# FMC_CONN_A1.net
KiCad netlist of a schematic drawn in Altium Designer
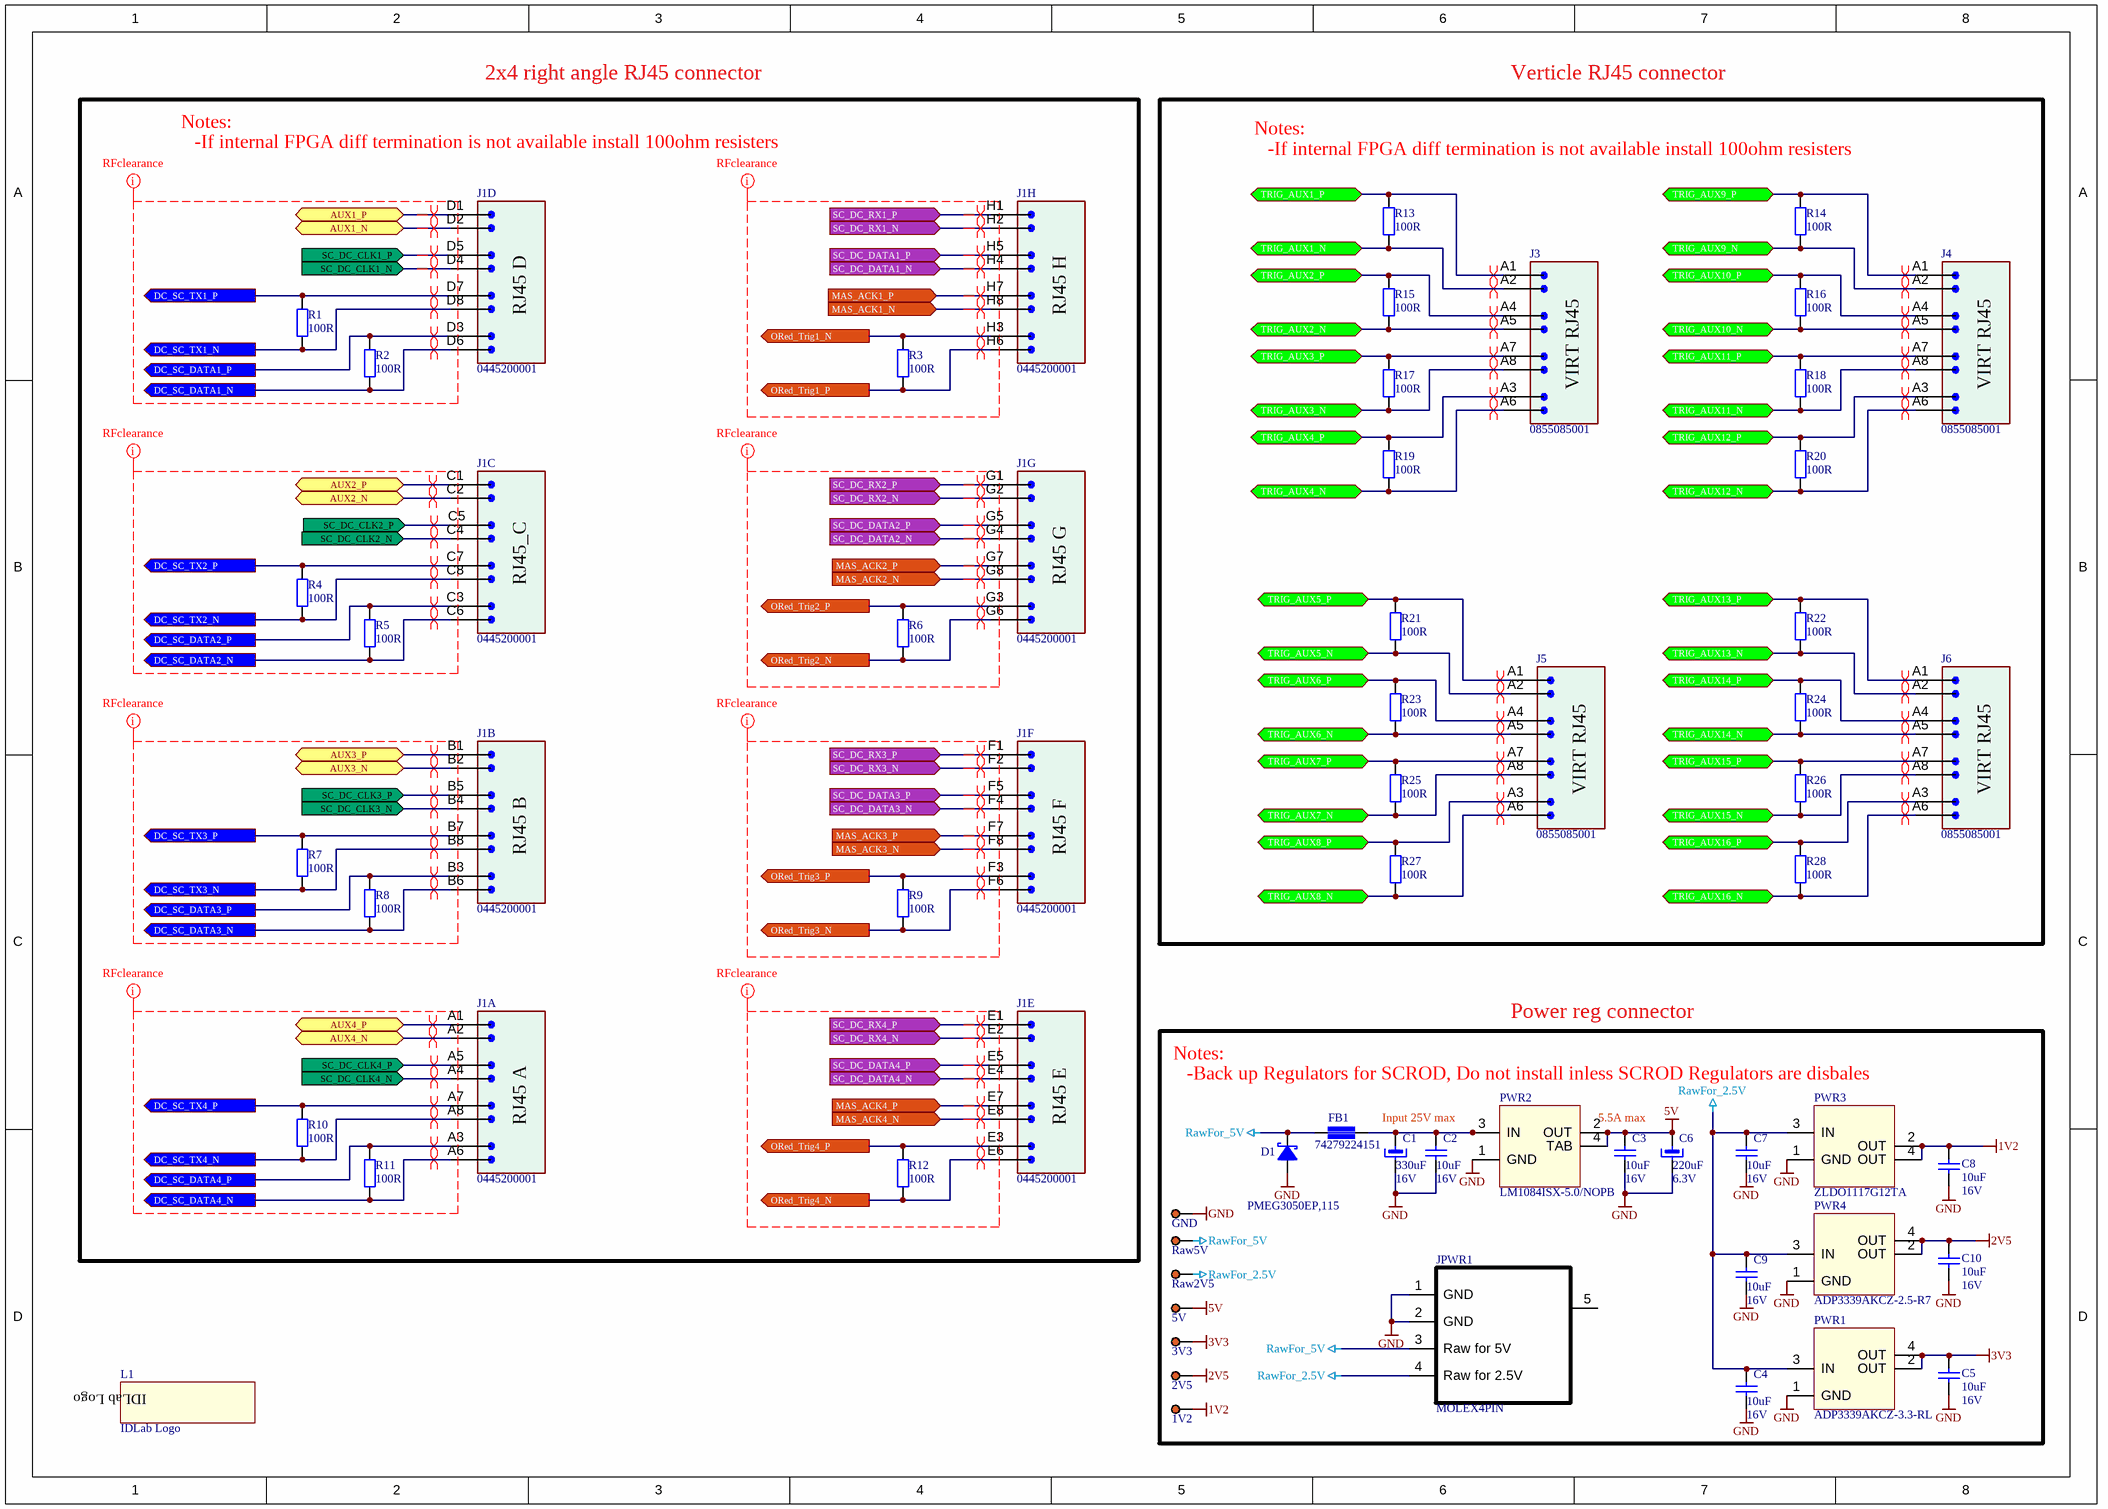
[diagram p0: FMC_CONN_A1.SchDoc]

(export (version "E")
  (design (tool "Eeschema 10.0.6"))
  (components
    (comp (ref "1V2")
      (value "SP1.5S")
      (footprint "SP1.5SQ")
      (description "Wire solder pin 1.5mm")
      (libsource (lib "Connectors_Old") (part "SP1.5S"))
    )
    (comp (ref "2V5")
      (value "SP1.5S")
      (footprint "SP1.5SQ")
      (description "Wire solder pin 1.5mm")
      (libsource (lib "Connectors_Old") (part "SP1.5S"))
    )
    (comp (ref "3V3")
      (value "SP1.5S")
      (footprint "SP1.5SQ")
      (description "Wire solder pin 1.5mm")
      (libsource (lib "Connectors_Old") (part "SP1.5S"))
    )
    (comp (ref "5V")
      (value "SP1.5S")
      (footprint "SP1.5SQ")
      (description "Wire solder pin 1.5mm")
      (libsource (lib "Connectors_Old") (part "SP1.5S"))
    )
    (comp (ref "C1")
      (value "330uF")
      (footprint "CTC-D7343-43")
      (description "330µF Molded Tantalum - Polymer Capacitors 16V")
      (fields (field (name "MANUFACTURER") "Kemet") (field (name "VOLTAGE RATING") "16V"))
      (libsource (lib "BMD") (part "CAPT7343_330U_16V"))
    )
    (comp (ref "C2")
      (value "10uF")
      (footprint "CC1206N1R")
      (description "10µF 16V Ceramic Capacitor X7R 1206")
      (fields (field (name "MANUFACTURER") "TDK") (field (name "VOLTAGE RATING") "16V"))
      (libsource (lib "BMD") (part "CAPCC1206_10U_16VX7R"))
    )
    (comp (ref "C3")
      (value "10uF")
      (footprint "CC1206N1R")
      (description "10µF 16V Ceramic Capacitor X7R 1206")
      (fields (field (name "MANUFACTURER") "TDK") (field (name "VOLTAGE RATING") "16V"))
      (libsource (lib "BMD") (part "CAPCC1206_10U_16VX7R"))
    )
    (comp (ref "C4")
      (value "10uF")
      (footprint "CC1206N1R")
      (description "10µF 16V Ceramic Capacitor X7R 1206")
      (fields (field (name "MANUFACTURER") "TDK") (field (name "VOLTAGE RATING") "16V"))
      (libsource (lib "BMD") (part "CAPCC1206_10U_16VX7R"))
    )
    (comp (ref "C5")
      (value "10uF")
      (footprint "CC1206N1R")
      (description "10µF 16V Ceramic Capacitor X7R 1206")
      (fields (field (name "MANUFACTURER") "TDK") (field (name "VOLTAGE RATING") "16V"))
      (libsource (lib "BMD") (part "CAPCC1206_10U_16VX7R"))
    )
    (comp (ref "C6")
      (value "220uF")
      (footprint "CTC-D7343-43")
      (description "220µF 6.3V Aluminum - Polymer Capacitors")
      (fields (field (name "MANUFACTURER") "Panasonic") (field (name "VOLTAGE RATING") "6.3V"))
      (libsource (lib "BMD") (part "CAPT7343_220U_6.3V"))
    )
    (comp (ref "C7")
      (value "10uF")
      (footprint "CC1206N1R")
      (description "10µF 16V Ceramic Capacitor X7R 1206")
      (fields (field (name "MANUFACTURER") "TDK") (field (name "VOLTAGE RATING") "16V"))
      (libsource (lib "BMD") (part "CAPCC1206_10U_16VX7R"))
    )
    (comp (ref "C8")
      (value "10uF")
      (footprint "CC1206N1R")
      (description "10µF 16V Ceramic Capacitor X7R 1206")
      (fields (field (name "MANUFACTURER") "TDK") (field (name "VOLTAGE RATING") "16V"))
      (libsource (lib "BMD") (part "CAPCC1206_10U_16VX7R"))
    )
    (comp (ref "C9")
      (value "10uF")
      (footprint "CC1206N1R")
      (description "10µF 16V Ceramic Capacitor X7R 1206")
      (fields (field (name "MANUFACTURER") "TDK") (field (name "VOLTAGE RATING") "16V"))
      (libsource (lib "BMD") (part "CAPCC1206_10U_16VX7R"))
    )
    (comp (ref "C10")
      (value "10uF")
      (footprint "CC1206N1R")
      (description "10µF 16V Ceramic Capacitor X7R 1206")
      (fields (field (name "MANUFACTURER") "TDK") (field (name "VOLTAGE RATING") "16V"))
      (libsource (lib "BMD") (part "CAPCC1206_10U_16VX7R"))
    )
    (comp (ref "D1")
      (value "PMEG3050EP,115")
      (footprint "SOD128")
      (description "DIODE SCHOTTKY 30V 5A SOD128  500ns 0.36Vf")
      (fields (field (name "MANUFACTURER") "NXP"))
      (libsource (lib "BMD") (part "Schottky_Diodes_5A_30V"))
    )
    (comp (ref "FB1")
      (value "74279224151")
      (footprint "FB2220N1R")
      (description "Feritte filter smd 2220 5A 10mRdc 150Rac")
      (fields (field (name "MANUFACTURER") "Wurth"))
      (libsource (lib "Induct-filter") (part "FB2220-74279224151"))
    )
    (comp (ref "GND")
      (value "SP1.5S")
      (footprint "SP1.5SQ")
      (description "Wire solder pin 1.5mm")
      (libsource (lib "Connectors_Old") (part "SP1.5S"))
    )
    (comp (ref "J1")
      (value "0445200001")
      (footprint "2X4 RJ45")
      (description "CONN MOD JACK 8P8C R/A SHIELDED")
      (fields (field (name "MANUFACTURER") "Molex, LLC"))
      (libsource (lib "IDlab") (part "2x4 RJ45 CONN"))
    )
    (comp (ref "J3")
      (value "0855085001")
      (footprint "VIRT RJ45")
      (description "CONN MOD JACK 8P8C R/A SHIELDED")
      (fields (field (name "MANUFACTURER") "Molex, LLC"))
      (libsource (lib "IDlab") (part "VIRT RJ45 CONN"))
    )
    (comp (ref "J4")
      (value "0855085001")
      (footprint "VIRT RJ45")
      (description "CONN MOD JACK 8P8C R/A SHIELDED")
      (fields (field (name "MANUFACTURER") "Molex, LLC"))
      (libsource (lib "IDlab") (part "VIRT RJ45 CONN"))
    )
    (comp (ref "J5")
      (value "0855085001")
      (footprint "VIRT RJ45")
      (description "CONN MOD JACK 8P8C R/A SHIELDED")
      (fields (field (name "MANUFACTURER") "Molex, LLC"))
      (libsource (lib "IDlab") (part "VIRT RJ45 CONN"))
    )
    (comp (ref "J6")
      (value "0855085001")
      (footprint "VIRT RJ45")
      (description "CONN MOD JACK 8P8C R/A SHIELDED")
      (fields (field (name "MANUFACTURER") "Molex, LLC"))
      (libsource (lib "IDlab") (part "VIRT RJ45 CONN"))
    )
    (comp (ref "JPWR1")
      (value "MOLEX4PIN")
      (footprint "PcbLib1:MOLEX_4PIN")
      (libsource (lib "Transition_Board") (part "MOLEX4PIN"))
    )
    (comp (ref "L1")
      (value "IDLab Logo")
      (footprint "IDLab logo")
      (libsource (lib "BMD") (part "IDLab Logo"))
    )
    (comp (ref "PWR1")
      (value "ADP3339AKCZ-3.3-RL")
      (footprint "SOT223")
      (description "IC REG LDO 3.3V 1.5A SOT223-3")
      (fields (field (name "MANUFACTURER") "Analog Devices Inc."))
      (libsource (lib "BMD") (part "3V3 REG LDO"))
    )
    (comp (ref "PWR2")
      (value "LM1084ISX-5.0/NOPB")
      (footprint "TO-263-4 DDPAK")
      (description "IC REG LDO 5V 5A DDPAK/TO-263-3")
      (fields (field (name "MANUFACTURER") "Texas Instruments"))
      (libsource (lib "BMD") (part "5V 5.5A REG LDO"))
    )
    (comp (ref "PWR3")
      (value "ZLDO1117G12TA")
      (footprint "SOT223")
      (description "IC REG LDO 1.2V 1A SOT223-3")
      (fields (field (name "MANUFACTURER") "Diodes Incorporated"))
      (libsource (lib "BMD") (part "1V2 REG LDO"))
    )
    (comp (ref "PWR4")
      (value "ADP3339AKCZ-2.5-R7")
      (footprint "SOT223")
      (description "IC REG LDO 2.5V 1.5A SOT223-3")
      (fields (field (name "MANUFACTURER") "Analog Devices Inc."))
      (libsource (lib "BMD") (part "2V5 REG LDO"))
    )
    (comp (ref "R1")
      (value "100R")
      (footprint "RC0402N1R")
      (description "RES SMD 100 OHM 1% 1/10W 0402")
      (fields (field (name "MANUFACTURER") "Panasonic"))
      (libsource (lib "BMD") (part "RES0402-100R-1%100PPM"))
    )
    (comp (ref "R2")
      (value "100R")
      (footprint "RC0402N1R")
      (description "RES SMD 100 OHM 1% 1/10W 0402")
      (fields (field (name "MANUFACTURER") "Panasonic"))
      (libsource (lib "BMD") (part "RES0402-100R-1%100PPM"))
    )
    (comp (ref "R3")
      (value "100R")
      (footprint "RC0402N1R")
      (description "RES SMD 100 OHM 1% 1/10W 0402")
      (fields (field (name "MANUFACTURER") "Panasonic"))
      (libsource (lib "BMD") (part "RES0402-100R-1%100PPM"))
    )
    (comp (ref "R4")
      (value "100R")
      (footprint "RC0402N1R")
      (description "RES SMD 100 OHM 1% 1/10W 0402")
      (fields (field (name "MANUFACTURER") "Panasonic"))
      (libsource (lib "BMD") (part "RES0402-100R-1%100PPM"))
    )
    (comp (ref "R5")
      (value "100R")
      (footprint "RC0402N1R")
      (description "RES SMD 100 OHM 1% 1/10W 0402")
      (fields (field (name "MANUFACTURER") "Panasonic"))
      (libsource (lib "BMD") (part "RES0402-100R-1%100PPM"))
    )
    (comp (ref "R6")
      (value "100R")
      (footprint "RC0402N1R")
      (description "RES SMD 100 OHM 1% 1/10W 0402")
      (fields (field (name "MANUFACTURER") "Panasonic"))
      (libsource (lib "BMD") (part "RES0402-100R-1%100PPM"))
    )
    (comp (ref "R7")
      (value "100R")
      (footprint "RC0402N1R")
      (description "RES SMD 100 OHM 1% 1/10W 0402")
      (fields (field (name "MANUFACTURER") "Panasonic"))
      (libsource (lib "BMD") (part "RES0402-100R-1%100PPM"))
    )
    (comp (ref "R8")
      (value "100R")
      (footprint "RC0402N1R")
      (description "RES SMD 100 OHM 1% 1/10W 0402")
      (fields (field (name "MANUFACTURER") "Panasonic"))
      (libsource (lib "BMD") (part "RES0402-100R-1%100PPM"))
    )
    (comp (ref "R9")
      (value "100R")
      (footprint "RC0402N1R")
      (description "RES SMD 100 OHM 1% 1/10W 0402")
      (fields (field (name "MANUFACTURER") "Panasonic"))
      (libsource (lib "BMD") (part "RES0402-100R-1%100PPM"))
    )
    (comp (ref "R10")
      (value "100R")
      (footprint "RC0402N1R")
      (description "RES SMD 100 OHM 1% 1/10W 0402")
      (fields (field (name "MANUFACTURER") "Panasonic"))
      (libsource (lib "BMD") (part "RES0402-100R-1%100PPM"))
    )
    (comp (ref "R11")
      (value "100R")
      (footprint "RC0402N1R")
      (description "RES SMD 100 OHM 1% 1/10W 0402")
      (fields (field (name "MANUFACTURER") "Panasonic"))
      (libsource (lib "BMD") (part "RES0402-100R-1%100PPM"))
    )
    (comp (ref "R12")
      (value "100R")
      (footprint "RC0402N1R")
      (description "RES SMD 100 OHM 1% 1/10W 0402")
      (fields (field (name "MANUFACTURER") "Panasonic"))
      (libsource (lib "BMD") (part "RES0402-100R-1%100PPM"))
    )
    (comp (ref "R13")
      (value "100R")
      (footprint "RC0402N1R")
      (description "RES SMD 100 OHM 1% 1/10W 0402")
      (fields (field (name "MANUFACTURER") "Panasonic"))
      (libsource (lib "BMD") (part "RES0402-100R-1%100PPM"))
    )
    (comp (ref "R14")
      (value "100R")
      (footprint "RC0402N1R")
      (description "RES SMD 100 OHM 1% 1/10W 0402")
      (fields (field (name "MANUFACTURER") "Panasonic"))
      (libsource (lib "BMD") (part "RES0402-100R-1%100PPM"))
    )
    (comp (ref "R15")
      (value "100R")
      (footprint "RC0402N1R")
      (description "RES SMD 100 OHM 1% 1/10W 0402")
      (fields (field (name "MANUFACTURER") "Panasonic"))
      (libsource (lib "BMD") (part "RES0402-100R-1%100PPM"))
    )
    (comp (ref "R16")
      (value "100R")
      (footprint "RC0402N1R")
      (description "RES SMD 100 OHM 1% 1/10W 0402")
      (fields (field (name "MANUFACTURER") "Panasonic"))
      (libsource (lib "BMD") (part "RES0402-100R-1%100PPM"))
    )
    (comp (ref "R17")
      (value "100R")
      (footprint "RC0402N1R")
      (description "RES SMD 100 OHM 1% 1/10W 0402")
      (fields (field (name "MANUFACTURER") "Panasonic"))
      (libsource (lib "BMD") (part "RES0402-100R-1%100PPM"))
    )
    (comp (ref "R18")
      (value "100R")
      (footprint "RC0402N1R")
      (description "RES SMD 100 OHM 1% 1/10W 0402")
      (fields (field (name "MANUFACTURER") "Panasonic"))
      (libsource (lib "BMD") (part "RES0402-100R-1%100PPM"))
    )
    (comp (ref "R19")
      (value "100R")
      (footprint "RC0402N1R")
      (description "RES SMD 100 OHM 1% 1/10W 0402")
      (fields (field (name "MANUFACTURER") "Panasonic"))
      (libsource (lib "BMD") (part "RES0402-100R-1%100PPM"))
    )
    (comp (ref "R20")
      (value "100R")
      (footprint "RC0402N1R")
      (description "RES SMD 100 OHM 1% 1/10W 0402")
      (fields (field (name "MANUFACTURER") "Panasonic"))
      (libsource (lib "BMD") (part "RES0402-100R-1%100PPM"))
    )
    (comp (ref "R21")
      (value "100R")
      (footprint "RC0402N1R")
      (description "RES SMD 100 OHM 1% 1/10W 0402")
      (fields (field (name "MANUFACTURER") "Panasonic"))
      (libsource (lib "BMD") (part "RES0402-100R-1%100PPM"))
    )
    (comp (ref "R22")
      (value "100R")
      (footprint "RC0402N1R")
      (description "RES SMD 100 OHM 1% 1/10W 0402")
      (fields (field (name "MANUFACTURER") "Panasonic"))
      (libsource (lib "BMD") (part "RES0402-100R-1%100PPM"))
    )
    (comp (ref "R23")
      (value "100R")
      (footprint "RC0402N1R")
      (description "RES SMD 100 OHM 1% 1/10W 0402")
      (fields (field (name "MANUFACTURER") "Panasonic"))
      (libsource (lib "BMD") (part "RES0402-100R-1%100PPM"))
    )
    (comp (ref "R24")
      (value "100R")
      (footprint "RC0402N1R")
      (description "RES SMD 100 OHM 1% 1/10W 0402")
      (fields (field (name "MANUFACTURER") "Panasonic"))
      (libsource (lib "BMD") (part "RES0402-100R-1%100PPM"))
    )
    (comp (ref "R25")
      (value "100R")
      (footprint "RC0402N1R")
      (description "RES SMD 100 OHM 1% 1/10W 0402")
      (fields (field (name "MANUFACTURER") "Panasonic"))
      (libsource (lib "BMD") (part "RES0402-100R-1%100PPM"))
    )
    (comp (ref "R26")
      (value "100R")
      (footprint "RC0402N1R")
      (description "RES SMD 100 OHM 1% 1/10W 0402")
      (fields (field (name "MANUFACTURER") "Panasonic"))
      (libsource (lib "BMD") (part "RES0402-100R-1%100PPM"))
    )
    (comp (ref "R27")
      (value "100R")
      (footprint "RC0402N1R")
      (description "RES SMD 100 OHM 1% 1/10W 0402")
      (fields (field (name "MANUFACTURER") "Panasonic"))
      (libsource (lib "BMD") (part "RES0402-100R-1%100PPM"))
    )
    (comp (ref "R28")
      (value "100R")
      (footprint "RC0402N1R")
      (description "RES SMD 100 OHM 1% 1/10W 0402")
      (fields (field (name "MANUFACTURER") "Panasonic"))
      (libsource (lib "BMD") (part "RES0402-100R-1%100PPM"))
    )
    (comp (ref "Raw2V5")
      (value "SP1.5S")
      (footprint "SP1.5SQ")
      (description "Wire solder pin 1.5mm")
      (libsource (lib "Connectors_Old") (part "SP1.5S"))
    )
    (comp (ref "Raw5V")
      (value "SP1.5S")
      (footprint "SP1.5SQ")
      (description "Wire solder pin 1.5mm")
      (libsource (lib "Connectors_Old") (part "SP1.5S"))
    )
  )
  (nets
    (net (code "1") (name "/AUX1_N") (class "Default")
      (node (ref "J1") (pin "D2") (pinfunction "D2_D2") (pintype "passive"))
    )
    (net (code "2") (name "/AUX1_P") (class "Default")
      (node (ref "J1") (pin "D1") (pinfunction "D1_D1") (pintype "passive"))
    )
    (net (code "3") (name "/AUX2_N") (class "Default")
      (node (ref "J1") (pin "C2") (pinfunction "C2_C2") (pintype "passive"))
    )
    (net (code "4") (name "/AUX2_P") (class "Default")
      (node (ref "J1") (pin "C1") (pinfunction "C1_C1") (pintype "passive"))
    )
    (net (code "5") (name "/AUX3_N") (class "Default")
      (node (ref "J1") (pin "B2") (pinfunction "B2_B2") (pintype "passive"))
    )
    (net (code "6") (name "/AUX3_P") (class "Default")
      (node (ref "J1") (pin "B1") (pinfunction "B1_B1") (pintype "passive"))
    )
    (net (code "7") (name "/AUX4_N") (class "Default")
      (node (ref "J1") (pin "A2") (pinfunction "A2_A2") (pintype "passive"))
    )
    (net (code "8") (name "/AUX4_P") (class "Default")
      (node (ref "J1") (pin "A1") (pinfunction "A1_A1") (pintype "passive"))
    )
    (net (code "9") (name "/DC_SC_DATA1_N") (class "Default")
      (node (ref "J1") (pin "D6") (pinfunction "D6_D6") (pintype "passive"))
      (node (ref "R2") (pin "1") (pinfunction "1_1") (pintype "passive"))
    )
    (net (code "10") (name "/DC_SC_DATA1_P") (class "Default")
      (node (ref "J1") (pin "D3") (pinfunction "D3_D3") (pintype "passive"))
      (node (ref "R2") (pin "2") (pinfunction "2_2") (pintype "passive"))
    )
    (net (code "11") (name "/DC_SC_DATA2_N") (class "Default")
      (node (ref "J1") (pin "C6") (pinfunction "C6_C6") (pintype "passive"))
      (node (ref "R5") (pin "1") (pinfunction "1_1") (pintype "passive"))
    )
    (net (code "12") (name "/DC_SC_DATA2_P") (class "Default")
      (node (ref "J1") (pin "C3") (pinfunction "C3_C3") (pintype "passive"))
      (node (ref "R5") (pin "2") (pinfunction "2_2") (pintype "passive"))
    )
    (net (code "13") (name "/DC_SC_DATA3_N") (class "Default")
      (node (ref "J1") (pin "B6") (pinfunction "B6_B6") (pintype "passive"))
      (node (ref "R8") (pin "1") (pinfunction "1_1") (pintype "passive"))
    )
    (net (code "14") (name "/DC_SC_DATA3_P") (class "Default")
      (node (ref "J1") (pin "B3") (pinfunction "B3_B3") (pintype "passive"))
      (node (ref "R8") (pin "2") (pinfunction "2_2") (pintype "passive"))
    )
    (net (code "15") (name "/DC_SC_DATA4_N") (class "Default")
      (node (ref "J1") (pin "A6") (pinfunction "A6_A6") (pintype "passive"))
      (node (ref "R11") (pin "1") (pinfunction "1_1") (pintype "passive"))
    )
    (net (code "16") (name "/DC_SC_DATA4_P") (class "Default")
      (node (ref "J1") (pin "A3") (pinfunction "A3_A3") (pintype "passive"))
      (node (ref "R11") (pin "2") (pinfunction "2_2") (pintype "passive"))
    )
    (net (code "17") (name "/DC_SC_TX1_N") (class "Default")
      (node (ref "J1") (pin "D8") (pinfunction "D8_D8") (pintype "passive"))
      (node (ref "R1") (pin "1") (pinfunction "1_1") (pintype "passive"))
    )
    (net (code "18") (name "/DC_SC_TX1_P") (class "Default")
      (node (ref "J1") (pin "D7") (pinfunction "D7_D7") (pintype "passive"))
      (node (ref "R1") (pin "2") (pinfunction "2_2") (pintype "passive"))
    )
    (net (code "19") (name "/DC_SC_TX2_N") (class "Default")
      (node (ref "J1") (pin "C8") (pinfunction "C8_C8") (pintype "passive"))
      (node (ref "R4") (pin "1") (pinfunction "1_1") (pintype "passive"))
    )
    (net (code "20") (name "/DC_SC_TX2_P") (class "Default")
      (node (ref "J1") (pin "C7") (pinfunction "C7_C7") (pintype "passive"))
      (node (ref "R4") (pin "2") (pinfunction "2_2") (pintype "passive"))
    )
    (net (code "21") (name "/DC_SC_TX3_N") (class "Default")
      (node (ref "J1") (pin "B8") (pinfunction "B8_B8") (pintype "passive"))
      (node (ref "R7") (pin "1") (pinfunction "1_1") (pintype "passive"))
    )
    (net (code "22") (name "/DC_SC_TX3_P") (class "Default")
      (node (ref "J1") (pin "B7") (pinfunction "B7_B7") (pintype "passive"))
      (node (ref "R7") (pin "2") (pinfunction "2_2") (pintype "passive"))
    )
    (net (code "23") (name "/DC_SC_TX4_N") (class "Default")
      (node (ref "J1") (pin "A8") (pinfunction "A8_A8") (pintype "passive"))
      (node (ref "R10") (pin "1") (pinfunction "1_1") (pintype "passive"))
    )
    (net (code "24") (name "/DC_SC_TX4_P") (class "Default")
      (node (ref "J1") (pin "A7") (pinfunction "A7_A7") (pintype "passive"))
      (node (ref "R10") (pin "2") (pinfunction "2_2") (pintype "passive"))
    )
    (net (code "25") (name "/MAS_ACK1_N") (class "Default")
      (node (ref "J1") (pin "H8") (pinfunction "H8_H8") (pintype "passive"))
    )
    (net (code "26") (name "/MAS_ACK1_P") (class "Default")
      (node (ref "J1") (pin "H7") (pinfunction "H7_H7") (pintype "passive"))
    )
    (net (code "27") (name "/MAS_ACK2_N") (class "Default")
      (node (ref "J1") (pin "G8") (pinfunction "G8_G8") (pintype "passive"))
    )
    (net (code "28") (name "/MAS_ACK2_P") (class "Default")
      (node (ref "J1") (pin "G7") (pinfunction "G7_G7") (pintype "passive"))
    )
    (net (code "29") (name "/MAS_ACK3_N") (class "Default")
      (node (ref "J1") (pin "F8") (pinfunction "F8_F8") (pintype "passive"))
    )
    (net (code "30") (name "/MAS_ACK3_P") (class "Default")
      (node (ref "J1") (pin "F7") (pinfunction "F7_F7") (pintype "passive"))
    )
    (net (code "31") (name "/MAS_ACK4_N") (class "Default")
      (node (ref "J1") (pin "E8") (pinfunction "E8_E8") (pintype "passive"))
    )
    (net (code "32") (name "/MAS_ACK4_P") (class "Default")
      (node (ref "J1") (pin "E7") (pinfunction "E7_E7") (pintype "passive"))
    )
    (net (code "33") (name "/ORed_Trig1_N") (class "Default")
      (node (ref "J1") (pin "H3") (pinfunction "H3_H3") (pintype "passive"))
      (node (ref "R3") (pin "2") (pinfunction "2_2") (pintype "passive"))
    )
    (net (code "34") (name "/ORed_Trig1_P") (class "Default")
      (node (ref "J1") (pin "H6") (pinfunction "H6_H6") (pintype "passive"))
      (node (ref "R3") (pin "1") (pinfunction "1_1") (pintype "passive"))
    )
    (net (code "35") (name "/ORed_Trig2_N") (class "Default")
      (node (ref "J1") (pin "G6") (pinfunction "G6_G6") (pintype "passive"))
      (node (ref "R6") (pin "1") (pinfunction "1_1") (pintype "passive"))
    )
    (net (code "36") (name "/ORed_Trig2_P") (class "Default")
      (node (ref "J1") (pin "G3") (pinfunction "G3_G3") (pintype "passive"))
      (node (ref "R6") (pin "2") (pinfunction "2_2") (pintype "passive"))
    )
    (net (code "37") (name "/ORed_Trig3_N") (class "Default")
      (node (ref "J1") (pin "F6") (pinfunction "F6_F6") (pintype "passive"))
      (node (ref "R9") (pin "1") (pinfunction "1_1") (pintype "passive"))
    )
    (net (code "38") (name "/ORed_Trig3_P") (class "Default")
      (node (ref "J1") (pin "F3") (pinfunction "F3_F3") (pintype "passive"))
      (node (ref "R9") (pin "2") (pinfunction "2_2") (pintype "passive"))
    )
    (net (code "39") (name "/ORed_Trig4_N") (class "Default")
      (node (ref "J1") (pin "E6") (pinfunction "E6_E6") (pintype "passive"))
      (node (ref "R12") (pin "1") (pinfunction "1_1") (pintype "passive"))
    )
    (net (code "40") (name "/ORed_Trig4_P") (class "Default")
      (node (ref "J1") (pin "E3") (pinfunction "E3_E3") (pintype "passive"))
      (node (ref "R12") (pin "2") (pinfunction "2_2") (pintype "passive"))
    )
    (net (code "41") (name "/SC_DC_CLK1_N") (class "Default")
      (node (ref "J1") (pin "D4") (pinfunction "D4_D4") (pintype "passive"))
    )
    (net (code "42") (name "/SC_DC_CLK1_P") (class "Default")
      (node (ref "J1") (pin "D5") (pinfunction "D5_D5") (pintype "passive"))
    )
    (net (code "43") (name "/SC_DC_CLK2_N") (class "Default")
      (node (ref "J1") (pin "C4") (pinfunction "C4_C4") (pintype "passive"))
    )
    (net (code "44") (name "/SC_DC_CLK2_P") (class "Default")
      (node (ref "J1") (pin "C5") (pinfunction "C5_C5") (pintype "passive"))
    )
    (net (code "45") (name "/SC_DC_CLK3_N") (class "Default")
      (node (ref "J1") (pin "B4") (pinfunction "B5_B4") (pintype "passive"))
    )
    (net (code "46") (name "/SC_DC_CLK3_P") (class "Default")
      (node (ref "J1") (pin "B5") (pinfunction "B5_B5") (pintype "passive"))
    )
    (net (code "47") (name "/SC_DC_CLK4_N") (class "Default")
      (node (ref "J1") (pin "A4") (pinfunction "A4_A4") (pintype "passive"))
    )
    (net (code "48") (name "/SC_DC_CLK4_P") (class "Default")
      (node (ref "J1") (pin "A5") (pinfunction "A5_A5") (pintype "passive"))
    )
    (net (code "49") (name "/SC_DC_DATA1_N") (class "Default")
      (node (ref "J1") (pin "H4") (pinfunction "H4_H4") (pintype "passive"))
    )
    (net (code "50") (name "/SC_DC_DATA1_P") (class "Default")
      (node (ref "J1") (pin "H5") (pinfunction "H5_H5") (pintype "passive"))
    )
    (net (code "51") (name "/SC_DC_DATA2_N") (class "Default")
      (node (ref "J1") (pin "G4") (pinfunction "G4_G4") (pintype "passive"))
    )
    (net (code "52") (name "/SC_DC_DATA2_P") (class "Default")
      (node (ref "J1") (pin "G5") (pinfunction "G5_G5") (pintype "passive"))
    )
    (net (code "53") (name "/SC_DC_DATA3_N") (class "Default")
      (node (ref "J1") (pin "F4") (pinfunction "F4_F4") (pintype "passive"))
    )
    (net (code "54") (name "/SC_DC_DATA3_P") (class "Default")
      (node (ref "J1") (pin "F5") (pinfunction "F5_F5") (pintype "passive"))
    )
    (net (code "55") (name "/SC_DC_DATA4_N") (class "Default")
      (node (ref "J1") (pin "E4") (pinfunction "E4_E4") (pintype "passive"))
    )
    (net (code "56") (name "/SC_DC_DATA4_P") (class "Default")
      (node (ref "J1") (pin "E5") (pinfunction "E5_E5") (pintype "passive"))
    )
    (net (code "57") (name "/SC_DC_RX1_N") (class "Default")
      (node (ref "J1") (pin "H2") (pinfunction "H2_H2") (pintype "passive"))
    )
    (net (code "58") (name "/SC_DC_RX1_P") (class "Default")
      (node (ref "J1") (pin "H1") (pinfunction "H1_H1") (pintype "passive"))
    )
    (net (code "59") (name "/SC_DC_RX2_N") (class "Default")
      (node (ref "J1") (pin "G2") (pinfunction "G2_G2") (pintype "passive"))
    )
    (net (code "60") (name "/SC_DC_RX2_P") (class "Default")
      (node (ref "J1") (pin "G1") (pinfunction "G1_G1") (pintype "passive"))
    )
    (net (code "61") (name "/SC_DC_RX3_N") (class "Default")
      (node (ref "J1") (pin "F2") (pinfunction "F2_F2") (pintype "passive"))
    )
    (net (code "62") (name "/SC_DC_RX3_P") (class "Default")
      (node (ref "J1") (pin "F1") (pinfunction "F1_F1") (pintype "passive"))
    )
    (net (code "63") (name "/SC_DC_RX4_N") (class "Default")
      (node (ref "J1") (pin "E2") (pinfunction "E2_E2") (pintype "passive"))
    )
    (net (code "64") (name "/SC_DC_RX4_P") (class "Default")
      (node (ref "J1") (pin "E1") (pinfunction "E1_E1") (pintype "passive"))
    )
    (net (code "65") (name "/TRIG_AUX1_N") (class "Default")
      (node (ref "J3") (pin "A2") (pinfunction "A2_A2") (pintype "passive"))
      (node (ref "R13") (pin "1") (pinfunction "1_1") (pintype "passive"))
    )
    (net (code "66") (name "/TRIG_AUX1_P") (class "Default")
      (node (ref "J3") (pin "A1") (pinfunction "A1_A1") (pintype "passive"))
      (node (ref "R13") (pin "2") (pinfunction "2_2") (pintype "passive"))
    )
    (net (code "67") (name "/TRIG_AUX2_N") (class "Default")
      (node (ref "J3") (pin "A5") (pinfunction "A5_A5") (pintype "passive"))
      (node (ref "R15") (pin "1") (pinfunction "1_1") (pintype "passive"))
    )
    (net (code "68") (name "/TRIG_AUX2_P") (class "Default")
      (node (ref "J3") (pin "A4") (pinfunction "A4_A4") (pintype "passive"))
      (node (ref "R15") (pin "2") (pinfunction "2_2") (pintype "passive"))
    )
    (net (code "69") (name "/TRIG_AUX3_N") (class "Default")
      (node (ref "J3") (pin "A8") (pinfunction "A8_A8") (pintype "passive"))
      (node (ref "R17") (pin "1") (pinfunction "1_1") (pintype "passive"))
    )
    (net (code "70") (name "/TRIG_AUX3_P") (class "Default")
      (node (ref "J3") (pin "A7") (pinfunction "A7_A7") (pintype "passive"))
      (node (ref "R17") (pin "2") (pinfunction "2_2") (pintype "passive"))
    )
    (net (code "71") (name "/TRIG_AUX4_N") (class "Default")
      (node (ref "J3") (pin "A6") (pinfunction "A6_A6") (pintype "passive"))
      (node (ref "R19") (pin "1") (pinfunction "1_1") (pintype "passive"))
    )
    (net (code "72") (name "/TRIG_AUX4_P") (class "Default")
      (node (ref "J3") (pin "A3") (pinfunction "A3_A3") (pintype "passive"))
      (node (ref "R19") (pin "2") (pinfunction "2_2") (pintype "passive"))
    )
    (net (code "73") (name "/TRIG_AUX5_N") (class "Default")
      (node (ref "J5") (pin "A2") (pinfunction "A2_A2") (pintype "passive"))
      (node (ref "R21") (pin "1") (pinfunction "1_1") (pintype "passive"))
    )
    (net (code "74") (name "/TRIG_AUX5_P") (class "Default")
      (node (ref "J5") (pin "A1") (pinfunction "A1_A1") (pintype "passive"))
      (node (ref "R21") (pin "2") (pinfunction "2_2") (pintype "passive"))
    )
    (net (code "75") (name "/TRIG_AUX6_N") (class "Default")
      (node (ref "J5") (pin "A5") (pinfunction "A5_A5") (pintype "passive"))
      (node (ref "R23") (pin "1") (pinfunction "1_1") (pintype "passive"))
    )
    (net (code "76") (name "/TRIG_AUX6_P") (class "Default")
      (node (ref "J5") (pin "A4") (pinfunction "A4_A4") (pintype "passive"))
      (node (ref "R23") (pin "2") (pinfunction "2_2") (pintype "passive"))
    )
    (net (code "77") (name "/TRIG_AUX7_N") (class "Default")
      (node (ref "J5") (pin "A8") (pinfunction "A8_A8") (pintype "passive"))
      (node (ref "R25") (pin "1") (pinfunction "1_1") (pintype "passive"))
    )
    (net (code "78") (name "/TRIG_AUX7_P") (class "Default")
      (node (ref "J5") (pin "A7") (pinfunction "A7_A7") (pintype "passive"))
      (node (ref "R25") (pin "2") (pinfunction "2_2") (pintype "passive"))
    )
    (net (code "79") (name "/TRIG_AUX8_N") (class "Default")
      (node (ref "J5") (pin "A6") (pinfunction "A6_A6") (pintype "passive"))
      (node (ref "R27") (pin "1") (pinfunction "1_1") (pintype "passive"))
    )
    (net (code "80") (name "/TRIG_AUX8_P") (class "Default")
      (node (ref "J5") (pin "A3") (pinfunction "A3_A3") (pintype "passive"))
      (node (ref "R27") (pin "2") (pinfunction "2_2") (pintype "passive"))
    )
    (net (code "81") (name "/TRIG_AUX9_N") (class "Default")
      (node (ref "J4") (pin "A2") (pinfunction "A2_A2") (pintype "passive"))
      (node (ref "R14") (pin "1") (pinfunction "1_1") (pintype "passive"))
    )
    (net (code "82") (name "/TRIG_AUX9_P") (class "Default")
      (node (ref "J4") (pin "A1") (pinfunction "A1_A1") (pintype "passive"))
      (node (ref "R14") (pin "2") (pinfunction "2_2") (pintype "passive"))
    )
    (net (code "83") (name "/TRIG_AUX10_N") (class "Default")
      (node (ref "J4") (pin "A5") (pinfunction "A5_A5") (pintype "passive"))
      (node (ref "R16") (pin "1") (pinfunction "1_1") (pintype "passive"))
    )
    (net (code "84") (name "/TRIG_AUX10_P") (class "Default")
      (node (ref "J4") (pin "A4") (pinfunction "A4_A4") (pintype "passive"))
      (node (ref "R16") (pin "2") (pinfunction "2_2") (pintype "passive"))
    )
    (net (code "85") (name "/TRIG_AUX11_N") (class "Default")
      (node (ref "J4") (pin "A8") (pinfunction "A8_A8") (pintype "passive"))
      (node (ref "R18") (pin "1") (pinfunction "1_1") (pintype "passive"))
    )
    (net (code "86") (name "/TRIG_AUX11_P") (class "Default")
      (node (ref "J4") (pin "A7") (pinfunction "A7_A7") (pintype "passive"))
      (node (ref "R18") (pin "2") (pinfunction "2_2") (pintype "passive"))
    )
    (net (code "87") (name "/TRIG_AUX12_N") (class "Default")
      (node (ref "J4") (pin "A6") (pinfunction "A6_A6") (pintype "passive"))
      (node (ref "R20") (pin "1") (pinfunction "1_1") (pintype "passive"))
    )
    (net (code "88") (name "/TRIG_AUX12_P") (class "Default")
      (node (ref "J4") (pin "A3") (pinfunction "A3_A3") (pintype "passive"))
      (node (ref "R20") (pin "2") (pinfunction "2_2") (pintype "passive"))
    )
    (net (code "89") (name "/TRIG_AUX13_N") (class "Default")
      (node (ref "J6") (pin "A2") (pinfunction "A2_A2") (pintype "passive"))
      (node (ref "R22") (pin "1") (pinfunction "1_1") (pintype "passive"))
    )
    (net (code "90") (name "/TRIG_AUX13_P") (class "Default")
      (node (ref "J6") (pin "A1") (pinfunction "A1_A1") (pintype "passive"))
      (node (ref "R22") (pin "2") (pinfunction "2_2") (pintype "passive"))
    )
    (net (code "91") (name "/TRIG_AUX14_N") (class "Default")
      (node (ref "J6") (pin "A5") (pinfunction "A5_A5") (pintype "passive"))
      (node (ref "R24") (pin "1") (pinfunction "1_1") (pintype "passive"))
    )
    (net (code "92") (name "/TRIG_AUX14_P") (class "Default")
      (node (ref "J6") (pin "A4") (pinfunction "A4_A4") (pintype "passive"))
      (node (ref "R24") (pin "2") (pinfunction "2_2") (pintype "passive"))
    )
    (net (code "93") (name "/TRIG_AUX15_N") (class "Default")
      (node (ref "J6") (pin "A8") (pinfunction "A8_A8") (pintype "passive"))
      (node (ref "R26") (pin "1") (pinfunction "1_1") (pintype "passive"))
    )
    (net (code "94") (name "/TRIG_AUX15_P") (class "Default")
      (node (ref "J6") (pin "A7") (pinfunction "A7_A7") (pintype "passive"))
      (node (ref "R26") (pin "2") (pinfunction "2_2") (pintype "passive"))
    )
    (net (code "95") (name "/TRIG_AUX16_N") (class "Default")
      (node (ref "J6") (pin "A6") (pinfunction "A6_A6") (pintype "passive"))
      (node (ref "R28") (pin "1") (pinfunction "1_1") (pintype "passive"))
    )
    (net (code "96") (name "/TRIG_AUX16_P") (class "Default")
      (node (ref "J6") (pin "A3") (pinfunction "A3_A3") (pintype "passive"))
      (node (ref "R28") (pin "2") (pinfunction "2_2") (pintype "passive"))
    )
    (net (code "97") (name "1V2") (class "Default")
      (node (ref "1V2") (pin "1") (pinfunction "1_1") (pintype "passive"))
      (node (ref "C8") (pin "2") (pinfunction "2_2") (pintype "passive"))
      (node (ref "PWR3") (pin "2") (pinfunction "OUT_2") (pintype "passive"))
      (node (ref "PWR3") (pin "4") (pinfunction "OUT_4") (pintype "passive"))
    )
    (net (code "98") (name "2V5") (class "Default")
      (node (ref "2V5") (pin "1") (pinfunction "1_1") (pintype "passive"))
      (node (ref "C10") (pin "2") (pinfunction "2_2") (pintype "passive"))
      (node (ref "PWR4") (pin "2") (pinfunction "OUT_2") (pintype "passive"))
      (node (ref "PWR4") (pin "4") (pinfunction "OUT_4") (pintype "passive"))
    )
    (net (code "99") (name "3V3") (class "Default")
      (node (ref "3V3") (pin "1") (pinfunction "1_1") (pintype "passive"))
      (node (ref "C5") (pin "2") (pinfunction "2_2") (pintype "passive"))
      (node (ref "PWR1") (pin "2") (pinfunction "OUT_2") (pintype "passive"))
      (node (ref "PWR1") (pin "4") (pinfunction "OUT_4") (pintype "passive"))
    )
    (net (code "100") (name "5V") (class "Default")
      (node (ref "5V") (pin "1") (pinfunction "1_1") (pintype "passive"))
      (node (ref "C3") (pin "2") (pinfunction "2_2") (pintype "passive"))
      (node (ref "C6") (pin "1") (pinfunction "1_1") (pintype "passive"))
      (node (ref "PWR2") (pin "2") (pinfunction "OUT_2") (pintype "passive"))
      (node (ref "PWR2") (pin "4") (pinfunction "TAB_4") (pintype "passive"))
    )
    (net (code "101") (name "GND") (class "Default")
      (node (ref "C1") (pin "2") (pinfunction "2_2") (pintype "passive"))
      (node (ref "C10") (pin "1") (pinfunction "1_1") (pintype "passive"))
      (node (ref "C2") (pin "1") (pinfunction "1_1") (pintype "passive"))
      (node (ref "C3") (pin "1") (pinfunction "1_1") (pintype "passive"))
      (node (ref "C4") (pin "1") (pinfunction "1_1") (pintype "passive"))
      (node (ref "C5") (pin "1") (pinfunction "1_1") (pintype "passive"))
      (node (ref "C6") (pin "2") (pinfunction "2_2") (pintype "passive"))
      (node (ref "C7") (pin "1") (pinfunction "1_1") (pintype "passive"))
      (node (ref "C8") (pin "1") (pinfunction "1_1") (pintype "passive"))
      (node (ref "C9") (pin "1") (pinfunction "1_1") (pintype "passive"))
      (node (ref "D1") (pin "2") (pinfunction "A_2") (pintype "passive"))
      (node (ref "GND") (pin "1") (pinfunction "1_1") (pintype "passive"))
      (node (ref "JPWR1") (pin "1") (pinfunction "GND_1") (pintype "passive"))
      (node (ref "JPWR1") (pin "2") (pinfunction "GND_2") (pintype "passive"))
      (node (ref "PWR1") (pin "1") (pinfunction "GND_1") (pintype "passive"))
      (node (ref "PWR2") (pin "1") (pinfunction "GND_1") (pintype "passive"))
      (node (ref "PWR3") (pin "1") (pinfunction "GND_1") (pintype "passive"))
      (node (ref "PWR4") (pin "1") (pinfunction "GND_1") (pintype "passive"))
    )
    (net (code "102") (name "Net-(PWR2-IN)") (class "Default")
      (node (ref "C1") (pin "1") (pinfunction "1_1") (pintype "passive"))
      (node (ref "C2") (pin "2") (pinfunction "2_2") (pintype "passive"))
      (node (ref "FB1") (pin "2") (pinfunction "2_2") (pintype "passive"))
      (node (ref "PWR2") (pin "3") (pinfunction "IN_3") (pintype "passive"))
    )
    (net (code "103") (name "RawFor_2.5V") (class "Default")
      (node (ref "C4") (pin "2") (pinfunction "2_2") (pintype "passive"))
      (node (ref "C7") (pin "2") (pinfunction "2_2") (pintype "passive"))
      (node (ref "C9") (pin "2") (pinfunction "2_2") (pintype "passive"))
      (node (ref "JPWR1") (pin "4") (pinfunction "Raw_for_2.5V_4") (pintype "passive"))
      (node (ref "PWR1") (pin "3") (pinfunction "IN_3") (pintype "passive"))
      (node (ref "PWR3") (pin "3") (pinfunction "IN_3") (pintype "passive"))
      (node (ref "PWR4") (pin "3") (pinfunction "IN_3") (pintype "passive"))
      (node (ref "Raw2V5") (pin "1") (pinfunction "1_1") (pintype "passive"))
    )
    (net (code "104") (name "RawFor_5V") (class "Default")
      (node (ref "D1") (pin "1") (pinfunction "C_1") (pintype "passive"))
      (node (ref "FB1") (pin "1") (pinfunction "1_1") (pintype "passive"))
      (node (ref "JPWR1") (pin "3") (pinfunction "Raw_for_5V_3") (pintype "passive"))
      (node (ref "Raw5V") (pin "1") (pinfunction "1_1") (pintype "passive"))
    )
    (net (code "105") (name "unconnected-(JPWR1-Pad5)") (class "Default")
      (node (ref "JPWR1") (pin "5") (pinfunction "5_5") (pintype "passive"))
    )
  )
)
